# M_D_ext_power_old.net
KiCad netlist of a schematic drawn in EAGLE
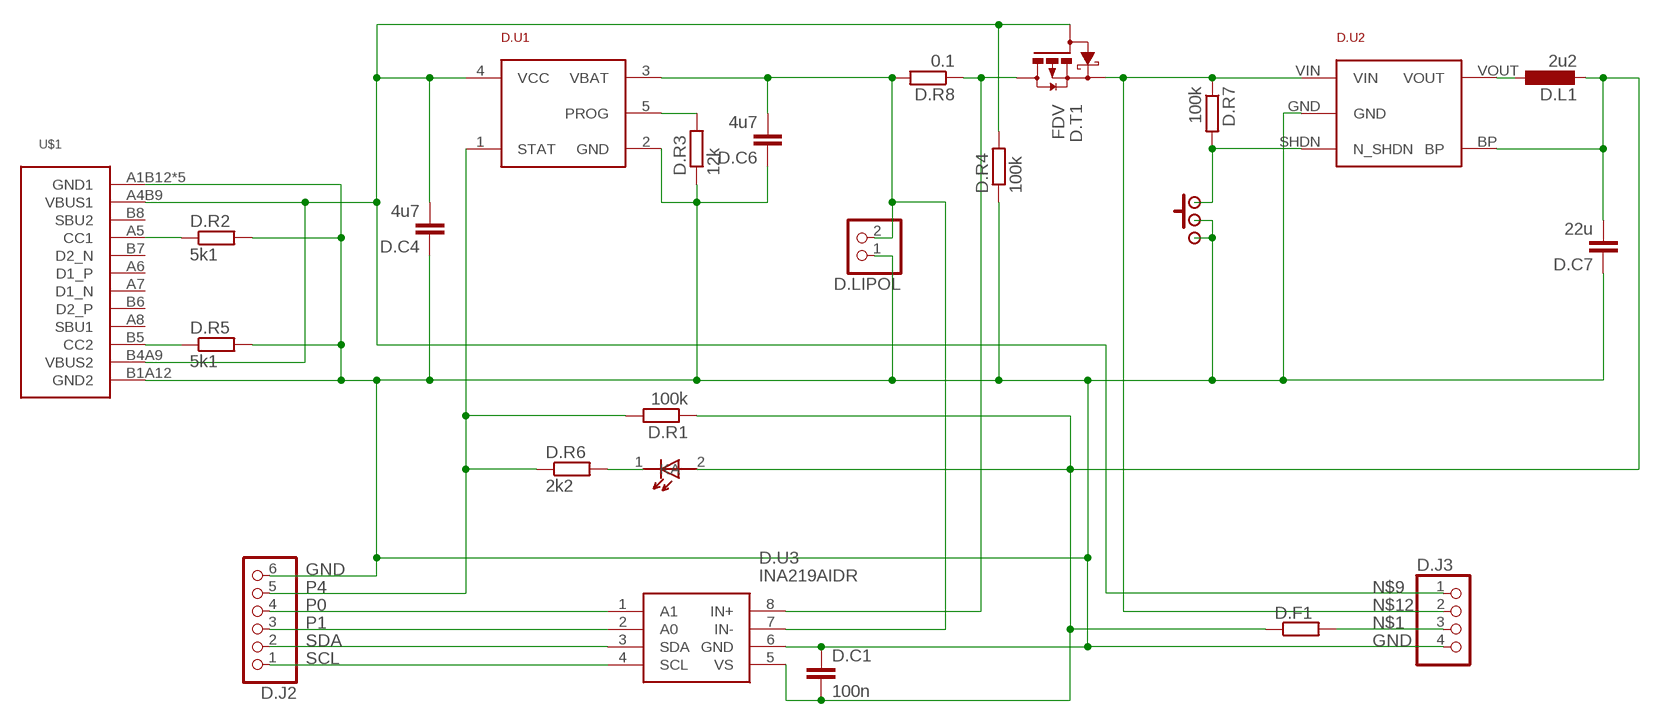
[diagram p0: schematic, sheet 1]

(export (version "E")
  (design (tool "Eeschema 10.0.6"))
  (components
    (comp (ref "D.C1")
      (value "100n")
      (footprint "eagle-import:C0603")
      (libsource (lib "eagle-import") (part "C-EUC0603"))
    )
    (comp (ref "D.C4")
      (value "4u7")
      (footprint "eagle-import:C0603")
      (libsource (lib "eagle-import") (part "C-EUC0603"))
    )
    (comp (ref "D.C6")
      (value "4u7")
      (footprint "eagle-import:C0603")
      (libsource (lib "eagle-import") (part "C-EUC0603"))
    )
    (comp (ref "D.C7")
      (value "22u")
      (footprint "eagle-import:C0805")
      (libsource (lib "eagle-import") (part "C-EUC0805"))
    )
    (comp (ref "D.D1")
      (value "LED_1.8")
      (footprint "eagle-import:LED_1.8")
      (libsource (lib "eagle-import") (part "LED_1.8"))
    )
    (comp (ref "D.F1")
      (value "R-EU_R0805")
      (footprint "eagle-import:R0805")
      (libsource (lib "eagle-import") (part "R-EU_R0805"))
    )
    (comp (ref "D.J2")
      (value "PINHD-1X6")
      (footprint "eagle-import:1X06")
      (libsource (lib "eagle-import") (part "PINHD-1X6"))
    )
    (comp (ref "D.J3")
      (value "PINHD-1X4")
      (footprint "eagle-import:1X04")
      (libsource (lib "eagle-import") (part "PINHD-1X4"))
    )
    (comp (ref "D.L1")
      (value "2u2")
      (footprint "eagle-import:L3230M")
      (libsource (lib "eagle-import") (part "L-EUL3230M"))
    )
    (comp (ref "D.LIPOL")
      (value "PINHD-1X2")
      (footprint "eagle-import:1X02")
      (libsource (lib "eagle-import") (part "PINHD-1X2"))
    )
    (comp (ref "D.ON/OFF/RESET")
      (value "SWITCH")
      (footprint "eagle-import:SWITCH")
      (libsource (lib "eagle-import") (part "SWITCH"))
    )
    (comp (ref "D.R1")
      (value "100k")
      (footprint "eagle-import:R0603")
      (libsource (lib "eagle-import") (part "R-EU_R0603"))
    )
    (comp (ref "D.R2")
      (value "5k1")
      (footprint "eagle-import:R0603")
      (libsource (lib "eagle-import") (part "R-EU_R0603"))
    )
    (comp (ref "D.R3")
      (value "12k")
      (footprint "eagle-import:R0603")
      (libsource (lib "eagle-import") (part "R-EU_R0603"))
    )
    (comp (ref "D.R4")
      (value "100k")
      (footprint "eagle-import:R0603")
      (libsource (lib "eagle-import") (part "R-EU_R0603"))
    )
    (comp (ref "D.R5")
      (value "5k1")
      (footprint "eagle-import:R0603")
      (libsource (lib "eagle-import") (part "R-EU_R0603"))
    )
    (comp (ref "D.R6")
      (value "2k2")
      (footprint "eagle-import:R0603")
      (libsource (lib "eagle-import") (part "R-EU_R0603"))
    )
    (comp (ref "D.R7")
      (value "100k")
      (footprint "eagle-import:R0603")
      (libsource (lib "eagle-import") (part "R-EU_R0603"))
    )
    (comp (ref "D.R8")
      (value "0.1")
      (footprint "eagle-import:R0805")
      (libsource (lib "eagle-import") (part "R-EU_R0805"))
    )
    (comp (ref "D.T1")
      (value "FDV")
      (footprint "eagle-import:SOT23")
      (libsource (lib "eagle-import") (part "P-MOSFET-FDV304P"))
    )
    (comp (ref "D.U1")
      (value "MCP")
      (footprint "eagle-import:SOT23-5")
      (libsource (lib "eagle-import") (part "MCP73831"))
    )
    (comp (ref "D.U2")
      (value "LM3671_3.3")
      (footprint "eagle-import:SOT32-5")
      (libsource (lib "eagle-import") (part "STABILISER_APE8865"))
    )
    (comp (ref "D.U3")
      (value "INA219AIDR")
      (footprint "eagle-import:SOIC127P600X175-8N")
      (fields (field (name "MOUSER_PART_NUMBER") "595-INA219AIDR"))
      (libsource (lib "eagle-import") (part "INA219AIDR"))
    )
    (comp (ref "U$1")
      (value "USB-C")
      (footprint "eagle-import:USB-C")
      (libsource (lib "eagle-import") (part "USB-C"))
    )
  )
  (nets
    (net (code "1") (name "/GND") (class "Default")
      (node (ref "D.C1") (pin "1") (pinfunction "1_1") (pintype "passive"))
      (node (ref "D.C4") (pin "1") (pinfunction "1_1") (pintype "passive"))
      (node (ref "D.C6") (pin "1") (pinfunction "1_1") (pintype "passive"))
      (node (ref "D.C7") (pin "1") (pinfunction "1_1") (pintype "passive"))
      (node (ref "D.J2") (pin "6") (pinfunction "6_6") (pintype "passive"))
      (node (ref "D.J3") (pin "4") (pinfunction "4_4") (pintype "passive"))
      (node (ref "D.LIPOL") (pin "1") (pinfunction "1_1") (pintype "passive"))
      (node (ref "D.ON/OFF/RESET") (pin "P$2") (pinfunction "P$2_P$2") (pintype "bidirectional"))
      (node (ref "D.ON/OFF/RESET") (pin "P$3") (pinfunction "P$3_P$3") (pintype "bidirectional"))
      (node (ref "D.ON/OFF/RESET") (pin "P$5") (pinfunction "P$3_P$5") (pintype "bidirectional"))
      (node (ref "D.R2") (pin "2") (pinfunction "2_2") (pintype "passive"))
      (node (ref "D.R3") (pin "1") (pinfunction "1_1") (pintype "passive"))
      (node (ref "D.R4") (pin "1") (pinfunction "1_1") (pintype "passive"))
      (node (ref "D.R5") (pin "2") (pinfunction "2_2") (pintype "passive"))
      (node (ref "D.U1") (pin "2") (pinfunction "GND_2") (pintype "bidirectional"))
      (node (ref "D.U2") (pin "GND") (pinfunction "GND_GND") (pintype "bidirectional"))
      (node (ref "D.U3") (pin "6") (pinfunction "GND_6") (pintype "bidirectional"))
      (node (ref "U$1") (pin "A1B12") (pinfunction "GND1_A1B12") (pintype "bidirectional"))
      (node (ref "U$1") (pin "B1A12") (pinfunction "GND2_B1A12") (pintype "bidirectional"))
      (node (ref "U$1") (pin "SH1") (pinfunction "GND1_SH1") (pintype "bidirectional"))
      (node (ref "U$1") (pin "SH2") (pinfunction "GND1_SH2") (pintype "bidirectional"))
      (node (ref "U$1") (pin "SH3") (pinfunction "GND1_SH3") (pintype "bidirectional"))
      (node (ref "U$1") (pin "SH4") (pinfunction "GND1_SH4") (pintype "bidirectional"))
    )
    (net (code "2") (name "/N$1") (class "Default")
      (node (ref "D.F1") (pin "2") (pinfunction "2_2") (pintype "passive"))
      (node (ref "D.J3") (pin "3") (pinfunction "3_3") (pintype "passive"))
    )
    (net (code "3") (name "/N$9") (class "Default")
      (node (ref "D.C4") (pin "2") (pinfunction "2_2") (pintype "passive"))
      (node (ref "D.J3") (pin "1") (pinfunction "1_1") (pintype "passive"))
      (node (ref "D.R4") (pin "2") (pinfunction "2_2") (pintype "passive"))
      (node (ref "D.T1") (pin "G") (pinfunction "G_G") (pintype "passive"))
      (node (ref "D.U1") (pin "4") (pinfunction "VCC_4") (pintype "bidirectional"))
      (node (ref "U$1") (pin "A4B9") (pinfunction "VBUS1_A4B9") (pintype "bidirectional"))
      (node (ref "U$1") (pin "B4A9") (pinfunction "VBUS2_B4A9") (pintype "bidirectional"))
    )
    (net (code "4") (name "/N$12") (class "Default")
      (node (ref "D.J3") (pin "2") (pinfunction "2_2") (pintype "passive"))
      (node (ref "D.R7") (pin "1") (pinfunction "1_1") (pintype "passive"))
      (node (ref "D.T1") (pin "S") (pinfunction "S_S") (pintype "passive"))
      (node (ref "D.U2") (pin "VIN") (pinfunction "VIN_VIN") (pintype "bidirectional"))
    )
    (net (code "5") (name "/P0") (class "Default")
      (node (ref "D.J2") (pin "4") (pinfunction "4_4") (pintype "passive"))
      (node (ref "D.U3") (pin "1") (pinfunction "A1_1") (pintype "bidirectional"))
    )
    (net (code "6") (name "/P1") (class "Default")
      (node (ref "D.J2") (pin "3") (pinfunction "3_3") (pintype "passive"))
      (node (ref "D.U3") (pin "2") (pinfunction "A0_2") (pintype "bidirectional"))
    )
    (net (code "7") (name "/P4") (class "Default")
      (node (ref "D.J2") (pin "5") (pinfunction "5_5") (pintype "passive"))
      (node (ref "D.R1") (pin "2") (pinfunction "2_2") (pintype "passive"))
      (node (ref "D.R6") (pin "1") (pinfunction "1_1") (pintype "passive"))
      (node (ref "D.U1") (pin "1") (pinfunction "STAT_1") (pintype "bidirectional"))
    )
    (net (code "8") (name "/SCL") (class "Default")
      (node (ref "D.J2") (pin "1") (pinfunction "1_1") (pintype "passive"))
      (node (ref "D.U3") (pin "4") (pinfunction "SCL_4") (pintype "bidirectional"))
    )
    (net (code "9") (name "/SDA") (class "Default")
      (node (ref "D.J2") (pin "2") (pinfunction "2_2") (pintype "passive"))
      (node (ref "D.U3") (pin "3") (pinfunction "SDA_3") (pintype "bidirectional"))
    )
    (net (code "10") (name "Net-(D.D1-A)") (class "Default")
      (node (ref "D.C1") (pin "2") (pinfunction "2_2") (pintype "passive"))
      (node (ref "D.C7") (pin "2") (pinfunction "2_2") (pintype "passive"))
      (node (ref "D.D1") (pin "2") (pinfunction "A_2") (pintype "bidirectional"))
      (node (ref "D.F1") (pin "1") (pinfunction "1_1") (pintype "passive"))
      (node (ref "D.L1") (pin "2") (pinfunction "2_2") (pintype "passive"))
      (node (ref "D.R1") (pin "1") (pinfunction "1_1") (pintype "passive"))
      (node (ref "D.U2") (pin "BP") (pinfunction "BP_BP") (pintype "bidirectional"))
      (node (ref "D.U3") (pin "5") (pinfunction "VS_5") (pintype "bidirectional"))
    )
    (net (code "11") (name "Net-(D.D1-K)") (class "Default")
      (node (ref "D.D1") (pin "1") (pinfunction "K_1") (pintype "bidirectional"))
      (node (ref "D.R6") (pin "2") (pinfunction "2_2") (pintype "passive"))
    )
    (net (code "12") (name "Net-(D.L1-Pad1)") (class "Default")
      (node (ref "D.L1") (pin "1") (pinfunction "1_1") (pintype "passive"))
      (node (ref "D.U2") (pin "VOUT") (pinfunction "VOUT_VOUT") (pintype "bidirectional"))
    )
    (net (code "13") (name "Net-(D.U1-PROG)") (class "Default")
      (node (ref "D.R3") (pin "2") (pinfunction "2_2") (pintype "passive"))
      (node (ref "D.U1") (pin "5") (pinfunction "PROG_5") (pintype "bidirectional"))
    )
    (net (code "14") (name "Net-(D.U1-VBAT)") (class "Default")
      (node (ref "D.C6") (pin "2") (pinfunction "2_2") (pintype "passive"))
      (node (ref "D.LIPOL") (pin "2") (pinfunction "2_2") (pintype "passive"))
      (node (ref "D.R8") (pin "2") (pinfunction "2_2") (pintype "passive"))
      (node (ref "D.U1") (pin "3") (pinfunction "VBAT_3") (pintype "bidirectional"))
      (node (ref "D.U3") (pin "7") (pinfunction "IN-_7") (pintype "bidirectional"))
    )
    (net (code "15") (name "Net-(D.U2-N_SHDN)") (class "Default")
      (node (ref "D.ON/OFF/RESET") (pin "P$1") (pinfunction "P$1_P$1") (pintype "bidirectional"))
      (node (ref "D.ON/OFF/RESET") (pin "P$4") (pinfunction "P$1_P$4") (pintype "bidirectional"))
      (node (ref "D.R7") (pin "2") (pinfunction "2_2") (pintype "passive"))
      (node (ref "D.U2") (pin "SHDN") (pinfunction "N_SHDN_SHDN") (pintype "bidirectional"))
    )
    (net (code "16") (name "Net-(D.U3-IN+)") (class "Default")
      (node (ref "D.R8") (pin "1") (pinfunction "1_1") (pintype "passive"))
      (node (ref "D.T1") (pin "D") (pinfunction "D_D") (pintype "passive"))
      (node (ref "D.U3") (pin "8") (pinfunction "IN+_8") (pintype "bidirectional"))
    )
    (net (code "17") (name "Net-(U$1-CC1)") (class "Default")
      (node (ref "D.R2") (pin "1") (pinfunction "1_1") (pintype "passive"))
      (node (ref "U$1") (pin "A5") (pinfunction "CC1_A5") (pintype "bidirectional"))
    )
    (net (code "18") (name "Net-(U$1-CC2)") (class "Default")
      (node (ref "D.R5") (pin "1") (pinfunction "1_1") (pintype "passive"))
      (node (ref "U$1") (pin "B5") (pinfunction "CC2_B5") (pintype "bidirectional"))
    )
    (net (code "19") (name "unconnected-(U$1-D1_N-PadA7)") (class "Default")
      (node (ref "U$1") (pin "A7") (pinfunction "D1_N_A7") (pintype "bidirectional"))
    )
    (net (code "20") (name "unconnected-(U$1-D1_P-PadA6)") (class "Default")
      (node (ref "U$1") (pin "A6") (pinfunction "D1_P_A6") (pintype "bidirectional"))
    )
    (net (code "21") (name "unconnected-(U$1-D2_N-PadB7)") (class "Default")
      (node (ref "U$1") (pin "B7") (pinfunction "D2_N_B7") (pintype "bidirectional"))
    )
    (net (code "22") (name "unconnected-(U$1-D2_P-PadB6)") (class "Default")
      (node (ref "U$1") (pin "B6") (pinfunction "D2_P_B6") (pintype "bidirectional"))
    )
    (net (code "23") (name "unconnected-(U$1-SBU1-PadA8)") (class "Default")
      (node (ref "U$1") (pin "A8") (pinfunction "SBU1_A8") (pintype "bidirectional"))
    )
    (net (code "24") (name "unconnected-(U$1-SBU2-PadB8)") (class "Default")
      (node (ref "U$1") (pin "B8") (pinfunction "SBU2_B8") (pintype "bidirectional"))
    )
  )
)
